# brush_driver.net
KiCad netlist of a schematic drawn in Altium Designer
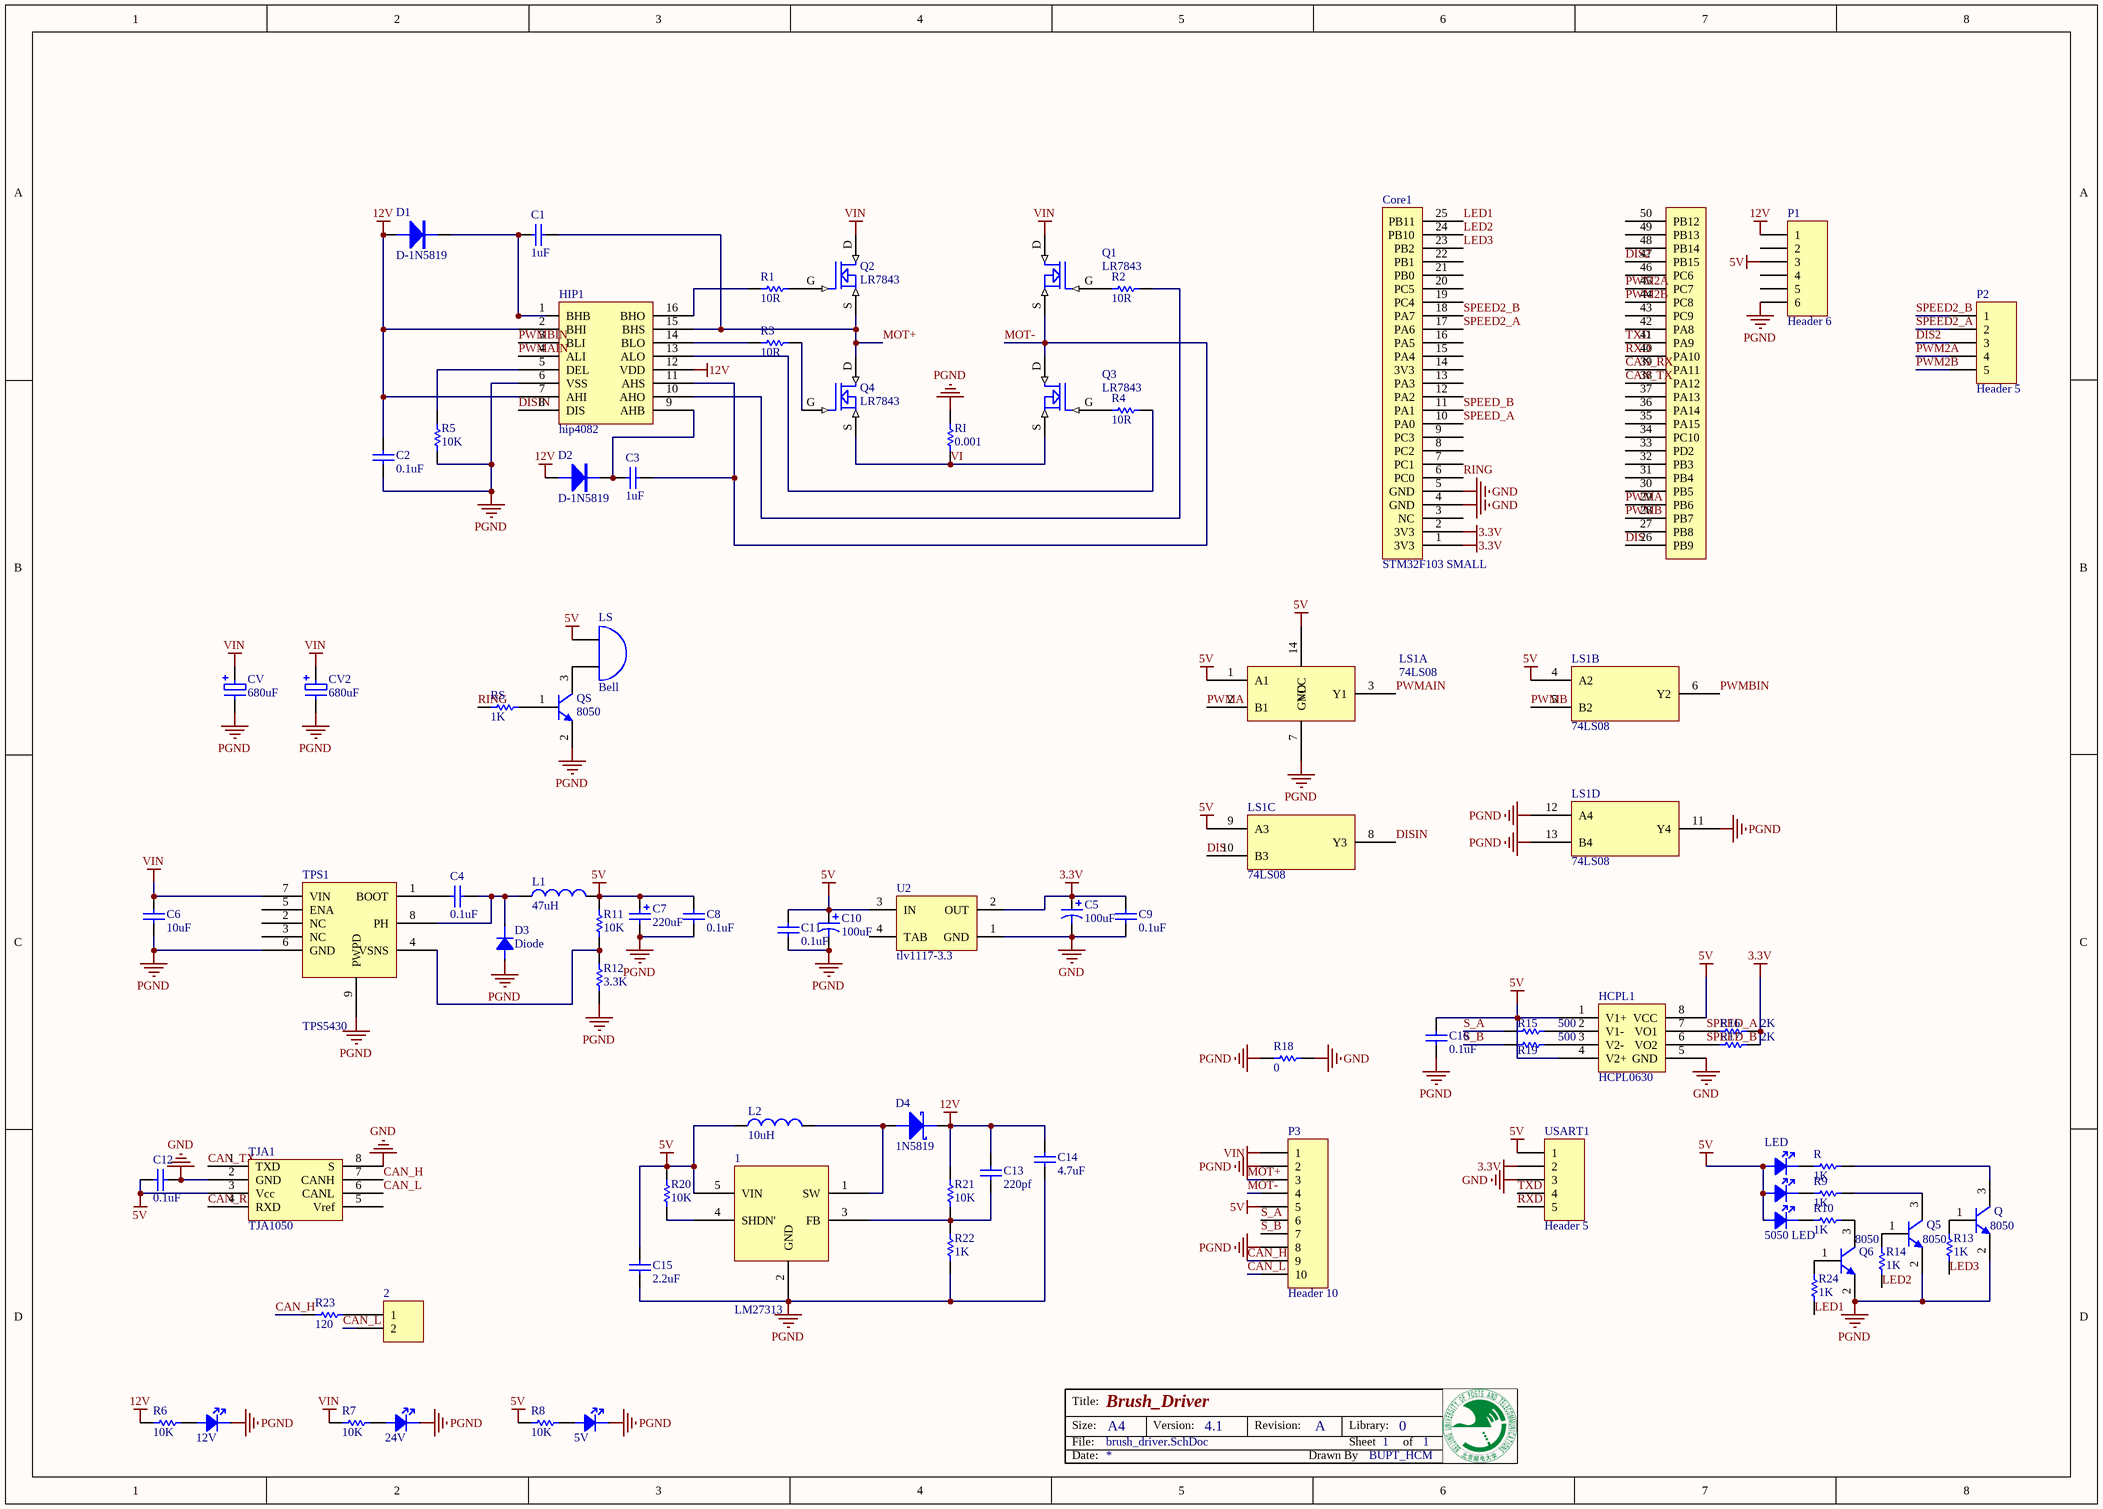
[diagram p0: brush_driver.SchDoc]

(export (version "E")
  (design (tool "Eeschema 10.0.6"))
  (components
    (comp (ref "1")
      (value "LM27313")
      (footprint "LM27313")
      (libsource (lib "K60-mainboard-v3.1") (part "LM27313"))
    )
    (comp (ref "2")
      (value "Header 2")
      (footprint "SIP2")
      (description "Header, 2-Pin")
      (fields (field (name "PUBLISHER") "Altium Limited"))
      (libsource (lib "Libraries_2014_0618") (part "Header 2"))
    )
    (comp (ref "5V")
      (value "lED")
      (footprint "0805D")
      (description "LED")
      (libsource (lib "K60-mainboard-v3.1") (part "00-D-LED"))
    )
    (comp (ref "12V")
      (value "lED")
      (footprint "0805D")
      (description "LED")
      (libsource (lib "K60-mainboard-v3.1") (part "00-D-LED"))
    )
    (comp (ref "24V")
      (value "lED")
      (footprint "0805D")
      (description "LED")
      (libsource (lib "K60-mainboard-v3.1") (part "00-D-LED"))
    )
    (comp (ref "C1")
      (value "1uF")
      (footprint "CAP-MLCC-0603")
      (description "Capacitor")
      (fields (field (name "Comment") "Cap") (field (name "PUBLISHER") "Altium Limited"))
      (libsource (lib "K60-mainboard-v3.1") (part "Cap"))
    )
    (comp (ref "C2")
      (value "0.1uF")
      (footprint "CAP-MLCC-0603")
      (description "Capacitor")
      (fields (field (name "Comment") "Cap") (field (name "PUBLISHER") "Altium Limited"))
      (libsource (lib "K60-mainboard-v3.1") (part "Cap"))
    )
    (comp (ref "C3")
      (value "1uF")
      (footprint "CAP-MLCC-0603")
      (description "Capacitor")
      (fields (field (name "Comment") "Cap") (field (name "PUBLISHER") "Altium Limited"))
      (libsource (lib "K60-mainboard-v3.1") (part "Cap"))
    )
    (comp (ref "C4")
      (value "0.1uF")
      (footprint "CAP-MLCC-0603")
      (description "Capacitor")
      (fields (field (name "Comment") "Cap") (field (name "PUBLISHER") "Altium Limited"))
      (libsource (lib "K60-mainboard-v3.1") (part "Cap"))
    )
    (comp (ref "C5")
      (value "100uF")
      (footprint "6032C")
      (description "Polarized Capacitor (Surface Mount)")
      (fields (field (name "Comment") "Cap Pol3") (field (name "PUBLISHER") "Altium Limited"))
      (libsource (lib "K60-mainboard-v3.1") (part "Cap Pol3"))
    )
    (comp (ref "C6")
      (value "10uF")
      (footprint "0805C")
      (description "Capacitor")
      (fields (field (name "Comment") "Cap") (field (name "PUBLISHER") "Altium Limited"))
      (libsource (lib "K60-mainboard-v3.1") (part "Cap"))
    )
    (comp (ref "C7")
      (value "220uF")
      (footprint "CAP-TAN-7343/CAPD")
      (description "Polarized Capacitor (Radial)")
      (fields (field (name "Comment") "Cap Pol1") (field (name "PUBLISHER") "Altium Limited"))
      (libsource (lib "K60-mainboard-v3.1") (part "Cap Pol1"))
    )
    (comp (ref "C8")
      (value "0.1uF")
      (footprint "CAP-MLCC-0603")
      (description "Capacitor")
      (fields (field (name "Comment") "Cap") (field (name "PUBLISHER") "Altium Limited"))
      (libsource (lib "K60-mainboard-v3.1") (part "Cap"))
    )
    (comp (ref "C9")
      (value "0.1uF")
      (footprint "CAP-MLCC-0603")
      (description "Capacitor")
      (fields (field (name "Comment") "Cap") (field (name "PUBLISHER") "Altium Limited"))
      (libsource (lib "K60-mainboard-v3.1") (part "Cap"))
    )
    (comp (ref "C10")
      (value "100uF")
      (footprint "6032C")
      (description "Polarized Capacitor (Surface Mount)")
      (fields (field (name "Comment") "Cap Pol3") (field (name "PUBLISHER") "Altium Limited"))
      (libsource (lib "K60-mainboard-v3.1") (part "Cap Pol3"))
    )
    (comp (ref "C11")
      (value "0.1uF")
      (footprint "CAP-MLCC-0603")
      (description "Capacitor")
      (fields (field (name "Comment") "Cap") (field (name "PUBLISHER") "Altium Limited"))
      (libsource (lib "K60-mainboard-v3.1") (part "Cap"))
    )
    (comp (ref "C12")
      (value "0.1uF")
      (footprint "CAP-MLCC-0603")
      (description "Capacitor")
      (fields (field (name "Comment") "Cap") (field (name "PUBLISHER") "Altium Limited"))
      (libsource (lib "K60-mainboard-v3.1") (part "Cap"))
    )
    (comp (ref "C13")
      (value "220pf")
      (footprint "CAP-MLCC-0603")
      (description "Capacitor")
      (fields (field (name "Comment") "Cap") (field (name "PUBLISHER") "Altium Limited"))
      (libsource (lib "K60-mainboard-v3.1") (part "Cap_1"))
    )
    (comp (ref "C14")
      (value "4.7uF")
      (footprint "CAP-MLCC-0603")
      (description "Capacitor")
      (fields (field (name "Comment") "Cap") (field (name "PUBLISHER") "Altium Limited"))
      (libsource (lib "K60-mainboard-v3.1") (part "Cap_1"))
    )
    (comp (ref "C15")
      (value "2.2uF")
      (footprint "CAP-MLCC-0603")
      (description "Capacitor")
      (fields (field (name "Comment") "Cap") (field (name "PUBLISHER") "Altium Limited"))
      (libsource (lib "K60-mainboard-v3.1") (part "Cap_1"))
    )
    (comp (ref "C16")
      (value "0.1uF")
      (footprint "CAP-MLCC-0603")
      (description "Capacitor")
      (fields (field (name "Comment") "Cap") (field (name "PUBLISHER") "Altium Limited"))
      (libsource (lib "K60-mainboard-v3.1") (part "Cap"))
    )
    (comp (ref "Core1")
      (value "STM32F103 SMALL")
      (footprint "STM32F103Small")
      (libsource (lib "K60-mainboard-v3.1") (part "STM32F103 SMALL"))
    )
    (comp (ref "CV")
      (value "680uF")
      (footprint "C_ELE")
      (description "电解电容")
      (fields (field (name "PUBLISHER") "Altium Limited"))
      (libsource (lib "Libraries_2014_0618") (part "CAP-ELE"))
    )
    (comp (ref "CV2")
      (value "680uF")
      (footprint "C_ELE")
      (description "电解电容")
      (fields (field (name "PUBLISHER") "Altium Limited"))
      (libsource (lib "Libraries_2014_0618") (part "CAP-ELE"))
    )
    (comp (ref "D1")
      (value "D-1N5819")
      (footprint "0805D")
      (description "Diode")
      (libsource (lib "常用器件") (part "D-1N5819"))
    )
    (comp (ref "D2")
      (value "D-1N5819")
      (footprint "0805D")
      (description "Diode")
      (libsource (lib "常用器件") (part "D-1N5819"))
    )
    (comp (ref "D3") (value "Diode") (footprint "SS34") (libsource (lib "K60-mainboard-v3.1") (part "Diode")))
    (comp (ref "D4")
      (value "1N5819")
      (footprint "0805D")
      (description "MBRA140T3")
      (libsource (lib "常用器件") (part "D-MBRA140T3"))
    )
    (comp (ref "HCPL1")
      (value "HCPL0630")
      (footprint "SOIC8")
      (libsource (lib "K60-mainboard-v3.1") (part "HCPL0630"))
    )
    (comp (ref "HIP1") (value "hip4082") (footprint "SOP16") (libsource (lib "元件库") (part "hip4082")))
    (comp (ref "L1")
      (value "47uH")
      (footprint "CD74")
      (description "Inductor")
      (fields (field (name "PUBLISHER") "Altium Limited"))
      (libsource (lib "smartcar_example") (part "Inductor"))
    )
    (comp (ref "L2")
      (value "10uH")
      (footprint "CD52")
      (description "Inductor")
      (fields (field (name "PUBLISHER") "Altium Limited"))
      (libsource (lib "smartcar_example") (part "Inductor"))
    )
    (comp (ref "LED")
      (value "5050 LED")
      (footprint "5050LED")
      (libsource (lib "K60-mainboard-v3.1") (part "5050 LED"))
    )
    (comp (ref "LS")
      (value "Bell")
      (footprint "Ring")
      (description "Electrical Bell")
      (fields (field (name "PUBLISHER") "Altium Limited"))
      (libsource (lib "附加元件") (part "Bell"))
    )
    (comp (ref "LS1")
      (value "74LS08")
      (footprint "SOJ-14")
      (libsource (lib "K60-mainboard-v3.1") (part "74LS08"))
    )
    (comp (ref "P1")
      (value "Header 6")
      (footprint "HDR1X6")
      (description "Header, 6-Pin")
      (fields (field (name "PUBLISHER") "Altium Limited"))
      (libsource (lib "K60-mainboard-v3.1") (part "Header 6"))
    )
    (comp (ref "P2")
      (value "Header 5")
      (footprint "HDR1X5")
      (description "Header, 5-Pin")
      (fields (field (name "PUBLISHER") "Altium Limited"))
      (libsource (lib "K60-mainboard-v3.1") (part "Header 5"))
    )
    (comp (ref "P3")
      (value "Header 10")
      (footprint "Green 10P")
      (description "Header, 10-Pin")
      (fields (field (name "PUBLISHER") "Altium Limited"))
      (libsource (lib "Libraries_2014_0618") (part "Header 10"))
    )
    (comp (ref "Q")
      (value "8050")
      (footprint "SOT-23B_N")
      (description "NPN Bipolar Transistor")
      (fields (field (name "PUBLISHER") "Altium Limited"))
      (libsource (lib "附加元件") (part "QNPN"))
    )
    (comp (ref "Q1")
      (value "LR7843")
      (footprint "LR7843")
      (libsource (lib "K60-mainboard-v3.1") (part "LR7843"))
    )
    (comp (ref "Q2")
      (value "LR7843")
      (footprint "LR7843")
      (libsource (lib "K60-mainboard-v3.1") (part "LR7843"))
    )
    (comp (ref "Q3")
      (value "LR7843")
      (footprint "LR7843")
      (libsource (lib "K60-mainboard-v3.1") (part "LR7843"))
    )
    (comp (ref "Q4")
      (value "LR7843")
      (footprint "LR7843")
      (libsource (lib "K60-mainboard-v3.1") (part "LR7843"))
    )
    (comp (ref "Q5")
      (value "8050")
      (footprint "SOT-23B_N")
      (description "NPN Bipolar Transistor")
      (fields (field (name "PUBLISHER") "Altium Limited"))
      (libsource (lib "附加元件") (part "QNPN"))
    )
    (comp (ref "Q6")
      (value "8050")
      (footprint "SOT-23B_N")
      (description "NPN Bipolar Transistor")
      (fields (field (name "PUBLISHER") "Altium Limited"))
      (libsource (lib "附加元件") (part "QNPN"))
    )
    (comp (ref "QS")
      (value "8050")
      (footprint "SOT-23B_N")
      (description "NPN Bipolar Transistor")
      (fields (field (name "PUBLISHER") "Altium Limited"))
      (libsource (lib "附加元件") (part "QNPN"))
    )
    (comp (ref "R")
      (value "1K")
      (footprint "RES-0603")
      (description "Resistor")
      (fields (field (name "Comment") "Res1") (field (name "PUBLISHER") "Altium Limited"))
      (libsource (lib "K60-mainboard-v3.1") (part "Res1"))
    )
    (comp (ref "R1")
      (value "10R")
      (footprint "RES-0603")
      (description "Resistor")
      (fields (field (name "Comment") "Res1") (field (name "PUBLISHER") "Altium Limited"))
      (libsource (lib "K60-mainboard-v3.1") (part "Res1"))
    )
    (comp (ref "R2")
      (value "10R")
      (footprint "RES-0603")
      (description "Resistor")
      (fields (field (name "Comment") "Res1") (field (name "PUBLISHER") "Altium Limited"))
      (libsource (lib "K60-mainboard-v3.1") (part "Res1"))
    )
    (comp (ref "R3")
      (value "10R")
      (footprint "RES-0603")
      (description "Resistor")
      (fields (field (name "Comment") "Res1") (field (name "PUBLISHER") "Altium Limited"))
      (libsource (lib "K60-mainboard-v3.1") (part "Res1"))
    )
    (comp (ref "R4")
      (value "10R")
      (footprint "RES-0603")
      (description "Resistor")
      (fields (field (name "Comment") "Res1") (field (name "PUBLISHER") "Altium Limited"))
      (libsource (lib "K60-mainboard-v3.1") (part "Res1"))
    )
    (comp (ref "R5")
      (value "10K")
      (footprint "RES-0603")
      (description "Resistor")
      (fields (field (name "Comment") "Res1") (field (name "PUBLISHER") "Altium Limited"))
      (libsource (lib "K60-mainboard-v3.1") (part "Res1"))
    )
    (comp (ref "R6")
      (value "10K")
      (footprint "RES-0603")
      (description "Resistor")
      (fields (field (name "Comment") "Res1") (field (name "PUBLISHER") "Altium Limited"))
      (libsource (lib "K60-mainboard-v3.1") (part "Res1"))
    )
    (comp (ref "R7")
      (value "10K")
      (footprint "RES-0603")
      (description "Resistor")
      (fields (field (name "Comment") "Res1") (field (name "PUBLISHER") "Altium Limited"))
      (libsource (lib "K60-mainboard-v3.1") (part "Res1"))
    )
    (comp (ref "R8")
      (value "10K")
      (footprint "RES-0603")
      (description "Resistor")
      (fields (field (name "Comment") "Res1") (field (name "PUBLISHER") "Altium Limited"))
      (libsource (lib "K60-mainboard-v3.1") (part "Res1"))
    )
    (comp (ref "R9")
      (value "1K")
      (footprint "RES-0603")
      (description "Resistor")
      (fields (field (name "Comment") "Res1") (field (name "PUBLISHER") "Altium Limited"))
      (libsource (lib "K60-mainboard-v3.1") (part "Res1"))
    )
    (comp (ref "R10")
      (value "1K")
      (footprint "RES-0603")
      (description "Resistor")
      (fields (field (name "Comment") "Res1") (field (name "PUBLISHER") "Altium Limited"))
      (libsource (lib "K60-mainboard-v3.1") (part "Res1"))
    )
    (comp (ref "R11")
      (value "10K")
      (footprint "RES-0603")
      (description "Resistor")
      (fields (field (name "Comment") "Res1") (field (name "PUBLISHER") "Altium Limited"))
      (libsource (lib "K60-mainboard-v3.1") (part "Res1"))
    )
    (comp (ref "R12")
      (value "3.3K")
      (footprint "RES-0603")
      (description "Resistor")
      (fields (field (name "Comment") "Res1") (field (name "PUBLISHER") "Altium Limited"))
      (libsource (lib "K60-mainboard-v3.1") (part "Res1"))
    )
    (comp (ref "R13")
      (value "1K")
      (footprint "RES-0603")
      (description "Resistor")
      (fields (field (name "Comment") "Res1") (field (name "PUBLISHER") "Altium Limited"))
      (libsource (lib "K60-mainboard-v3.1") (part "Res1"))
    )
    (comp (ref "R14")
      (value "1K")
      (footprint "RES-0603")
      (description "Resistor")
      (fields (field (name "Comment") "Res1") (field (name "PUBLISHER") "Altium Limited"))
      (libsource (lib "K60-mainboard-v3.1") (part "Res1"))
    )
    (comp (ref "R15")
      (value "500")
      (footprint "RES-0603")
      (description "Resistor")
      (fields (field (name "Comment") "Res1") (field (name "PUBLISHER") "Altium Limited"))
      (libsource (lib "K60-mainboard-v3.1") (part "Res1"))
    )
    (comp (ref "R16")
      (value "2K")
      (footprint "RES-0603")
      (description "Resistor")
      (fields (field (name "Comment") "Res1") (field (name "PUBLISHER") "Altium Limited"))
      (libsource (lib "K60-mainboard-v3.1") (part "Res1"))
    )
    (comp (ref "R17")
      (value "2K")
      (footprint "RES-0603")
      (description "Resistor")
      (fields (field (name "Comment") "Res1") (field (name "PUBLISHER") "Altium Limited"))
      (libsource (lib "K60-mainboard-v3.1") (part "Res1"))
    )
    (comp (ref "R18")
      (value "0")
      (footprint "RES-0603")
      (description "Resistor")
      (fields (field (name "Comment") "Res1") (field (name "PUBLISHER") "Altium Limited"))
      (libsource (lib "K60-mainboard-v3.1") (part "Res1"))
    )
    (comp (ref "R19")
      (value "500")
      (footprint "RES-0603")
      (description "Resistor")
      (fields (field (name "Comment") "Res1") (field (name "PUBLISHER") "Altium Limited"))
      (libsource (lib "K60-mainboard-v3.1") (part "Res1"))
    )
    (comp (ref "R20")
      (value "10K")
      (footprint "RES-0603")
      (description "Resistor")
      (fields (field (name "Comment") "Res1") (field (name "PUBLISHER") "Altium Limited"))
      (libsource (lib "K60-mainboard-v3.1") (part "Res1_1"))
    )
    (comp (ref "R21")
      (value "10K")
      (footprint "RES-0603")
      (description "Resistor")
      (fields (field (name "Comment") "Res1") (field (name "PUBLISHER") "Altium Limited"))
      (libsource (lib "K60-mainboard-v3.1") (part "Res1_1"))
    )
    (comp (ref "R22")
      (value "1K")
      (footprint "RES-0603")
      (description "Resistor")
      (fields (field (name "Comment") "Res1") (field (name "PUBLISHER") "Altium Limited"))
      (libsource (lib "K60-mainboard-v3.1") (part "Res1_1"))
    )
    (comp (ref "R23")
      (value "120")
      (footprint "RES-0603")
      (description "Resistor")
      (fields (field (name "Comment") "Res1") (field (name "PUBLISHER") "Altium Limited"))
      (libsource (lib "K60-mainboard-v3.1") (part "Res1"))
    )
    (comp (ref "R24")
      (value "1K")
      (footprint "RES-0603")
      (description "Resistor")
      (fields (field (name "Comment") "Res1") (field (name "PUBLISHER") "Altium Limited"))
      (libsource (lib "K60-mainboard-v3.1") (part "Res1"))
    )
    (comp (ref "RI")
      (value "0.001")
      (footprint "2512R")
      (description "Resistor")
      (fields (field (name "Comment") "Res1") (field (name "PUBLISHER") "Altium Limited"))
      (libsource (lib "K60-mainboard-v3.1") (part "Res1"))
    )
    (comp (ref "RS")
      (value "1K")
      (footprint "RES-0603")
      (description "Resistor")
      (fields (field (name "Comment") "Res1") (field (name "PUBLISHER") "Altium Limited"))
      (libsource (lib "K60-mainboard-v3.1") (part "Res1"))
    )
    (comp (ref "TJA1")
      (value "TJA1050")
      (footprint "TJA1050")
      (description "CAN总线收发器")
      (libsource (lib "Libraries_2014_0618") (part "TJA1050"))
    )
    (comp (ref "TPS1")
      (value "TPS5430")
      (footprint "TPS5430")
      (libsource (lib "K60-mainboard-v3.1") (part "TPS5430"))
    )
    (comp (ref "U2")
      (value "tlv1117-3.3")
      (footprint "LM1117")
      (description "800mA Low-Dropout Linear Regulator")
      (fields
        (field (name "PARTNUMBER") "LM1117IMP-5.0")
        (field (name "MANUFACTURER") "National Semiconductor")
        (field (name "PUBLISHER") "Altium Limited")
      )
      (libsource (lib "K60-mainboard-v3.1") (part "LM1117IMP-5.0"))
    )
    (comp (ref "USART1")
      (value "Header 5")
      (footprint "Green_5P")
      (description "Header, 5-Pin")
      (fields (field (name "PUBLISHER") "Altium Limited"))
      (libsource (lib "Libraries_2014_0618") (part "Header 5"))
    )
  )
  (nets
    (net (code "1") (name "/CAN_H") (class "Default")
      (node (ref "P3") (pin "9") (pinfunction "9_9") (pintype "passive"))
      (node (ref "R23") (pin "2") (pinfunction "2_2") (pintype "passive"))
      (node (ref "TJA1") (pin "7") (pinfunction "CANH_7") (pintype "passive"))
    )
    (net (code "2") (name "/CAN_L") (class "Default")
      (node (ref "2") (pin "2") (pinfunction "2_2") (pintype "passive"))
      (node (ref "P3") (pin "10") (pinfunction "10_10") (pintype "passive"))
      (node (ref "TJA1") (pin "6") (pinfunction "CANL_6") (pintype "passive"))
    )
    (net (code "3") (name "/CAN_RX") (class "Default")
      (node (ref "Core1") (pin "39") (pinfunction "PA11_39") (pintype "passive"))
      (node (ref "TJA1") (pin "4") (pinfunction "RXD_4") (pintype "passive"))
    )
    (net (code "4") (name "/CAN_TX") (class "Default")
      (node (ref "Core1") (pin "38") (pinfunction "PA12_38") (pintype "passive"))
      (node (ref "TJA1") (pin "1") (pinfunction "TXD_1") (pintype "passive"))
    )
    (net (code "5") (name "/DIS") (class "Default")
      (node (ref "Core1") (pin "26") (pinfunction "PB9_26") (pintype "passive"))
      (node (ref "LS1") (pin "10") (pinfunction "B3_10") (pintype "passive"))
    )
    (net (code "6") (name "/DIS2") (class "Default")
      (node (ref "Core1") (pin "47") (pinfunction "PB15_47") (pintype "passive"))
      (node (ref "P2") (pin "3") (pinfunction "3_3") (pintype "passive"))
    )
    (net (code "7") (name "/DISIN") (class "Default")
      (node (ref "HIP1") (pin "8") (pinfunction "DIS_8") (pintype "passive"))
      (node (ref "LS1") (pin "8") (pinfunction "Y3_8") (pintype "passive"))
    )
    (net (code "8") (name "/LED1") (class "Default")
      (node (ref "Core1") (pin "25") (pinfunction "PB11_25") (pintype "passive"))
      (node (ref "R24") (pin "2") (pinfunction "2_2") (pintype "passive"))
    )
    (net (code "9") (name "/LED2") (class "Default")
      (node (ref "Core1") (pin "24") (pinfunction "PB10_24") (pintype "passive"))
      (node (ref "R14") (pin "2") (pinfunction "2_2") (pintype "passive"))
    )
    (net (code "10") (name "/LED3") (class "Default")
      (node (ref "Core1") (pin "23") (pinfunction "PB2_23") (pintype "passive"))
      (node (ref "R13") (pin "2") (pinfunction "2_2") (pintype "passive"))
    )
    (net (code "11") (name "/MOT+") (class "Default")
      (node (ref "C1") (pin "1") (pinfunction "1_1") (pintype "passive"))
      (node (ref "HIP1") (pin "15") (pinfunction "BHS_15") (pintype "passive"))
      (node (ref "P3") (pin "3") (pinfunction "3_3") (pintype "passive"))
      (node (ref "Q2") (pin "S") (pinfunction "S_S") (pintype "input"))
      (node (ref "Q4") (pin "D") (pinfunction "D_D") (pintype "input"))
    )
    (net (code "12") (name "/MOT-") (class "Default")
      (node (ref "C3") (pin "1") (pinfunction "1_1") (pintype "passive"))
      (node (ref "HIP1") (pin "11") (pinfunction "AHS_11") (pintype "passive"))
      (node (ref "P3") (pin "4") (pinfunction "4_4") (pintype "passive"))
      (node (ref "Q1") (pin "S") (pinfunction "S_S") (pintype "input"))
      (node (ref "Q3") (pin "D") (pinfunction "D_D") (pintype "input"))
    )
    (net (code "13") (name "/PWM2A") (class "Default")
      (node (ref "Core1") (pin "45") (pinfunction "PC7_45") (pintype "passive"))
      (node (ref "P2") (pin "4") (pinfunction "4_4") (pintype "passive"))
    )
    (net (code "14") (name "/PWM2B") (class "Default")
      (node (ref "Core1") (pin "44") (pinfunction "PC8_44") (pintype "passive"))
      (node (ref "P2") (pin "5") (pinfunction "5_5") (pintype "passive"))
    )
    (net (code "15") (name "/PWMA") (class "Default")
      (node (ref "Core1") (pin "29") (pinfunction "PB6_29") (pintype "passive"))
      (node (ref "LS1") (pin "2") (pinfunction "B1_2") (pintype "passive"))
    )
    (net (code "16") (name "/PWMAIN") (class "Default")
      (node (ref "HIP1") (pin "4") (pinfunction "ALI_4") (pintype "passive"))
      (node (ref "LS1") (pin "3") (pinfunction "Y1_3") (pintype "passive"))
    )
    (net (code "17") (name "/PWMB") (class "Default")
      (node (ref "Core1") (pin "28") (pinfunction "PB7_28") (pintype "passive"))
      (node (ref "LS1") (pin "5") (pinfunction "B2_5") (pintype "passive"))
    )
    (net (code "18") (name "/PWMBIN") (class "Default")
      (node (ref "HIP1") (pin "3") (pinfunction "BLI_3") (pintype "passive"))
      (node (ref "LS1") (pin "6") (pinfunction "Y2_6") (pintype "passive"))
    )
    (net (code "19") (name "/RING") (class "Default")
      (node (ref "Core1") (pin "6") (pinfunction "PC0_6") (pintype "passive"))
      (node (ref "RS") (pin "2") (pinfunction "2_2") (pintype "passive"))
    )
    (net (code "20") (name "/RXD") (class "Default")
      (node (ref "Core1") (pin "40") (pinfunction "PA10_40") (pintype "passive"))
      (node (ref "USART1") (pin "5") (pinfunction "5_5") (pintype "passive"))
    )
    (net (code "21") (name "/SPEED2_A") (class "Default")
      (node (ref "Core1") (pin "17") (pinfunction "PA6_17") (pintype "passive"))
      (node (ref "P2") (pin "2") (pinfunction "2_2") (pintype "passive"))
    )
    (net (code "22") (name "/SPEED2_B") (class "Default")
      (node (ref "Core1") (pin "18") (pinfunction "PA7_18") (pintype "passive"))
      (node (ref "P2") (pin "1") (pinfunction "1_1") (pintype "passive"))
    )
    (net (code "23") (name "/SPEED_A") (class "Default")
      (node (ref "Core1") (pin "10") (pinfunction "PA0_10") (pintype "passive"))
      (node (ref "HCPL1") (pin "7") (pinfunction "VO1_7") (pintype "passive"))
      (node (ref "R16") (pin "1") (pinfunction "1_1") (pintype "passive"))
    )
    (net (code "24") (name "/SPEED_B") (class "Default")
      (node (ref "Core1") (pin "11") (pinfunction "PA1_11") (pintype "passive"))
      (node (ref "HCPL1") (pin "6") (pinfunction "VO2_6") (pintype "passive"))
      (node (ref "R17") (pin "1") (pinfunction "1_1") (pintype "passive"))
    )
    (net (code "25") (name "/S_A") (class "Default")
      (node (ref "P3") (pin "6") (pinfunction "6_6") (pintype "passive"))
      (node (ref "R15") (pin "1") (pinfunction "1_1") (pintype "passive"))
    )
    (net (code "26") (name "/S_B") (class "Default")
      (node (ref "P3") (pin "7") (pinfunction "7_7") (pintype "passive"))
      (node (ref "R19") (pin "1") (pinfunction "1_1") (pintype "passive"))
    )
    (net (code "27") (name "/TXD") (class "Default")
      (node (ref "Core1") (pin "41") (pinfunction "PA9_41") (pintype "passive"))
      (node (ref "USART1") (pin "4") (pinfunction "4_4") (pintype "passive"))
    )
    (net (code "28") (name "/VI") (class "Default")
      (node (ref "Q3") (pin "S") (pinfunction "S_S") (pintype "input"))
      (node (ref "Q4") (pin "S") (pinfunction "S_S") (pintype "input"))
      (node (ref "RI") (pin "1") (pinfunction "1_1") (pintype "passive"))
    )
    (net (code "29") (name "3.3V") (class "Default")
      (node (ref "C5") (pin "1") (pinfunction "1_1") (pintype "passive"))
      (node (ref "C9") (pin "1") (pinfunction "1_1") (pintype "passive"))
      (node (ref "Core1") (pin "1") (pinfunction "3V3_1") (pintype "passive"))
      (node (ref "Core1") (pin "2") (pinfunction "3V3_2") (pintype "passive"))
      (node (ref "R16") (pin "2") (pinfunction "2_2") (pintype "passive"))
      (node (ref "R17") (pin "2") (pinfunction "2_2") (pintype "passive"))
      (node (ref "U2") (pin "2") (pinfunction "OUT_2") (pintype "power_in"))
      (node (ref "USART1") (pin "2") (pinfunction "2_2") (pintype "passive"))
    )
    (net (code "30") (name "5V") (class "Default")
      (node (ref "1") (pin "5") (pinfunction "VIN_5") (pintype "passive"))
      (node (ref "C10") (pin "1") (pinfunction "1_1") (pintype "passive"))
      (node (ref "C11") (pin "1") (pinfunction "1_1") (pintype "passive"))
      (node (ref "C12") (pin "1") (pinfunction "1_1") (pintype "passive"))
      (node (ref "C15") (pin "2") (pinfunction "2_2") (pintype "passive"))
      (node (ref "C16") (pin "1") (pinfunction "1_1") (pintype "passive"))
      (node (ref "C7") (pin "1") (pinfunction "1_1") (pintype "passive"))
      (node (ref "C8") (pin "2") (pinfunction "2_2") (pintype "passive"))
      (node (ref "HCPL1") (pin "1") (pinfunction "V1+_1") (pintype "passive"))
      (node (ref "HCPL1") (pin "4") (pinfunction "V2+_4") (pintype "passive"))
      (node (ref "HCPL1") (pin "8") (pinfunction "VCC_8") (pintype "passive"))
      (node (ref "L1") (pin "2") (pinfunction "2_2") (pintype "passive"))
      (node (ref "L2") (pin "1") (pinfunction "1_1") (pintype "passive"))
      (node (ref "LED") (pin "A1") (pinfunction "1_A1") (pintype "passive"))
      (node (ref "LED") (pin "A2") (pinfunction "3_A2") (pintype "passive"))
      (node (ref "LED") (pin "A3") (pinfunction "5_A3") (pintype "passive"))
      (node (ref "LS") (pin "1") (pinfunction "A_1") (pintype "passive"))
      (node (ref "LS1") (pin "1") (pinfunction "A1_1") (pintype "passive"))
      (node (ref "LS1") (pin "14") (pinfunction "VCC_14") (pintype "passive"))
      (node (ref "LS1") (pin "4") (pinfunction "A2_4") (pintype "passive"))
      (node (ref "LS1") (pin "9") (pinfunction "A3_9") (pintype "passive"))
      (node (ref "P1") (pin "3") (pinfunction "3_3") (pintype "passive"))
      (node (ref "P3") (pin "5") (pinfunction "5_5") (pintype "passive"))
      (node (ref "R11") (pin "2") (pinfunction "2_2") (pintype "passive"))
      (node (ref "R20") (pin "1") (pinfunction "1_1") (pintype "passive"))
      (node (ref "R8") (pin "2") (pinfunction "2_2") (pintype "passive"))
      (node (ref "TJA1") (pin "3") (pinfunction "Vcc_3") (pintype "passive"))
      (node (ref "U2") (pin "3") (pinfunction "IN_3") (pintype "power_in"))
      (node (ref "USART1") (pin "1") (pinfunction "1_1") (pintype "passive"))
    )
    (net (code "31") (name "12V") (class "Default")
      (node (ref "C13") (pin "2") (pinfunction "2_2") (pintype "passive"))
      (node (ref "C14") (pin "2") (pinfunction "2_2") (pintype "passive"))
      (node (ref "C2") (pin "2") (pinfunction "2_2") (pintype "passive"))
      (node (ref "D1") (pin "A") (pinfunction "1_A") (pintype "passive"))
      (node (ref "D2") (pin "A") (pinfunction "1_A") (pintype "passive"))
      (node (ref "D4") (pin "K") (pinfunction "2_K") (pintype "passive"))
      (node (ref "HIP1") (pin "12") (pinfunction "VDD_12") (pintype "passive"))
      (node (ref "HIP1") (pin "2") (pinfunction "BHI_2") (pintype "passive"))
      (node (ref "HIP1") (pin "7") (pinfunction "AHI_7") (pintype "passive"))
      (node (ref "P1") (pin "1") (pinfunction "1_1") (pintype "passive"))
      (node (ref "R21") (pin "1") (pinfunction "1_1") (pintype "passive"))
      (node (ref "R6") (pin "2") (pinfunction "2_2") (pintype "passive"))
    )
    (net (code "32") (name "GND") (class "Default")
      (node (ref "C12") (pin "2") (pinfunction "2_2") (pintype "passive"))
      (node (ref "C5") (pin "2") (pinfunction "2_2") (pintype "passive"))
      (node (ref "C9") (pin "2") (pinfunction "2_2") (pintype "passive"))
      (node (ref "Core1") (pin "4") (pinfunction "GND_4") (pintype "passive"))
      (node (ref "Core1") (pin "5") (pinfunction "GND_5") (pintype "passive"))
      (node (ref "HCPL1") (pin "5") (pinfunction "GND_5") (pintype "passive"))
      (node (ref "R18") (pin "2") (pinfunction "2_2") (pintype "passive"))
      (node (ref "TJA1") (pin "2") (pinfunction "GND_2") (pintype "passive"))
      (node (ref "TJA1") (pin "8") (pinfunction "S_8") (pintype "passive"))
      (node (ref "U2") (pin "1") (pinfunction "GND_1") (pintype "power_in"))
      (node (ref "USART1") (pin "3") (pinfunction "3_3") (pintype "passive"))
    )
    (net (code "33") (name "Net-(1-FB)") (class "Default")
      (node (ref "1") (pin "3") (pinfunction "FB_3") (pintype "passive"))
      (node (ref "C13") (pin "1") (pinfunction "1_1") (pintype "passive"))
      (node (ref "R21") (pin "2") (pinfunction "2_2") (pintype "passive"))
      (node (ref "R22") (pin "1") (pinfunction "1_1") (pintype "passive"))
    )
    (net (code "34") (name "Net-(1-SHDN')") (class "Default")
      (node (ref "1") (pin "4") (pinfunction "SHDN'_4") (pintype "passive"))
      (node (ref "R20") (pin "2") (pinfunction "2_2") (pintype "passive"))
    )
    (net (code "35") (name "Net-(1-SW)") (class "Default")
      (node (ref "1") (pin "1") (pinfunction "SW_1") (pintype "passive"))
      (node (ref "D4") (pin "A") (pinfunction "1_A") (pintype "passive"))
      (node (ref "L2") (pin "2") (pinfunction "2_2") (pintype "passive"))
    )
    (net (code "36") (name "Net-(2-Pad1)") (class "Default")
      (node (ref "2") (pin "1") (pinfunction "1_1") (pintype "passive"))
      (node (ref "R23") (pin "1") (pinfunction "1_1") (pintype "passive"))
    )
    (net (code "37") (name "Net-(5V-1)") (class "Default")
      (node (ref "5V") (pin "A") (pinfunction "1_A") (pintype "passive"))
      (node (ref "R8") (pin "1") (pinfunction "1_1") (pintype "passive"))
    )
    (net (code "38") (name "Net-(12V-1)") (class "Default")
      (node (ref "12V") (pin "A") (pinfunction "1_A") (pintype "passive"))
      (node (ref "R6") (pin "1") (pinfunction "1_1") (pintype "passive"))
    )
    (net (code "39") (name "Net-(24V-1)") (class "Default")
      (node (ref "24V") (pin "A") (pinfunction "1_A") (pintype "passive"))
      (node (ref "R7") (pin "1") (pinfunction "1_1") (pintype "passive"))
    )
    (net (code "40") (name "Net-(D1-2)") (class "Default")
      (node (ref "C1") (pin "2") (pinfunction "2_2") (pintype "passive"))
      (node (ref "D1") (pin "K") (pinfunction "2_K") (pintype "passive"))
      (node (ref "HIP1") (pin "1") (pinfunction "BHB_1") (pintype "passive"))
    )
    (net (code "41") (name "Net-(D2-2)") (class "Default")
      (node (ref "C3") (pin "2") (pinfunction "2_2") (pintype "passive"))
      (node (ref "D2") (pin "K") (pinfunction "2_K") (pintype "passive"))
      (node (ref "HIP1") (pin "9") (pinfunction "AHB_9") (pintype "passive"))
    )
    (net (code "42") (name "Net-(D3-2)") (class "Default")
      (node (ref "C4") (pin "2") (pinfunction "2_2") (pintype "passive"))
      (node (ref "D3") (pin "K") (pinfunction "2_K") (pintype "passive"))
      (node (ref "L1") (pin "1") (pinfunction "1_1") (pintype "passive"))
      (node (ref "TPS1") (pin "8") (pinfunction "PH_8") (pintype "passive"))
    )
    (net (code "43") (name "Net-(HCPL1-V1-)") (class "Default")
      (node (ref "HCPL1") (pin "2") (pinfunction "V1-_2") (pintype "passive"))
      (node (ref "R15") (pin "2") (pinfunction "2_2") (pintype "passive"))
    )
    (net (code "44") (name "Net-(HCPL1-V2-)") (class "Default")
      (node (ref "HCPL1") (pin "3") (pinfunction "V2-_3") (pintype "passive"))
      (node (ref "R19") (pin "2") (pinfunction "2_2") (pintype "passive"))
    )
    (net (code "45") (name "Net-(HIP1-AHO)") (class "Default")
      (node (ref "HIP1") (pin "10") (pinfunction "AHO_10") (pintype "passive"))
      (node (ref "R2") (pin "2") (pinfunction "2_2") (pintype "passive"))
    )
    (net (code "46") (name "Net-(HIP1-ALO)") (class "Default")
      (node (ref "HIP1") (pin "13") (pinfunction "ALO_13") (pintype "passive"))
      (node (ref "R4") (pin "2") (pinfunction "2_2") (pintype "passive"))
    )
    (net (code "47") (name "Net-(HIP1-BHO)") (class "Default")
      (node (ref "HIP1") (pin "16") (pinfunction "BHO_16") (pintype "passive"))
      (node (ref "R1") (pin "2") (pinfunction "2_2") (pintype "passive"))
    )
    (net (code "48") (name "Net-(HIP1-BLO)") (class "Default")
      (node (ref "HIP1") (pin "14") (pinfunction "BLO_14") (pintype "passive"))
      (node (ref "R3") (pin "1") (pinfunction "1_1") (pintype "passive"))
    )
    (net (code "49") (name "Net-(HIP1-DEL)") (class "Default")
      (node (ref "HIP1") (pin "5") (pinfunction "DEL_5") (pintype "passive"))
      (node (ref "R5") (pin "2") (pinfunction "2_2") (pintype "passive"))
    )
    (net (code "50") (name "Net-(LED-2)") (class "Default")
      (node (ref "LED") (pin "K1") (pinfunction "2_K1") (pintype "passive"))
      (node (ref "R") (pin "2") (pinfunction "2_2") (pintype "passive"))
    )
    (net (code "51") (name "Net-(LED-4)") (class "Default")
      (node (ref "LED") (pin "K2") (pinfunction "4_K2") (pintype "passive"))
      (node (ref "R9") (pin "2") (pinfunction "2_2") (pintype "passive"))
    )
    (net (code "52") (name "Net-(LED-6)") (class "Default")
      (node (ref "LED") (pin "K3") (pinfunction "6_K3") (pintype "passive"))
      (node (ref "R10") (pin "2") (pinfunction "2_2") (pintype "passive"))
    )
    (net (code "53") (name "Net-(LS-B)") (class "Default")
      (node (ref "LS") (pin "2") (pinfunction "B_2") (pintype "passive"))
      (node (ref "QS") (pin "3") (pinfunction "C_3") (pintype "passive"))
    )
    (net (code "54") (name "Net-(Q-B)") (class "Default")
      (node (ref "Q") (pin "1") (pinfunction "B_1") (pintype "passive"))
      (node (ref "R13") (pin "1") (pinfunction "1_1") (pintype "passive"))
    )
    (net (code "55") (name "Net-(Q-C)") (class "Default")
      (node (ref "Q") (pin "3") (pinfunction "C_3") (pintype "passive"))
      (node (ref "R") (pin "1") (pinfunction "1_1") (pintype "passive"))
    )
    (net (code "56") (name "Net-(Q1-PadG)") (class "Default")
      (node (ref "Q1") (pin "G") (pinfunction "G_G") (pintype "input"))
      (node (ref "R2") (pin "1") (pinfunction "1_1") (pintype "passive"))
    )
    (net (code "57") (name "Net-(Q2-PadG)") (class "Default")
      (node (ref "Q2") (pin "G") (pinfunction "G_G") (pintype "input"))
      (node (ref "R1") (pin "1") (pinfunction "1_1") (pintype "passive"))
    )
    (net (code "58") (name "Net-(Q3-PadG)") (class "Default")
      (node (ref "Q3") (pin "G") (pinfunction "G_G") (pintype "input"))
      (node (ref "R4") (pin "1") (pinfunction "1_1") (pintype "passive"))
    )
    (net (code "59") (name "Net-(Q4-PadG)") (class "Default")
      (node (ref "Q4") (pin "G") (pinfunction "G_G") (pintype "input"))
      (node (ref "R3") (pin "2") (pinfunction "2_2") (pintype "passive"))
    )
    (net (code "60") (name "Net-(Q5-B)") (class "Default")
      (node (ref "Q5") (pin "1") (pinfunction "B_1") (pintype "passive"))
      (node (ref "R14") (pin "1") (pinfunction "1_1") (pintype "passive"))
    )
    (net (code "61") (name "Net-(Q5-C)") (class "Default")
      (node (ref "Q5") (pin "3") (pinfunction "C_3") (pintype "passive"))
      (node (ref "R9") (pin "1") (pinfunction "1_1") (pintype "passive"))
    )
    (net (code "62") (name "Net-(Q6-B)") (class "Default")
      (node (ref "Q6") (pin "1") (pinfunction "B_1") (pintype "passive"))
      (node (ref "R24") (pin "1") (pinfunction "1_1") (pintype "passive"))
    )
    (net (code "63") (name "Net-(Q6-C)") (class "Default")
      (node (ref "Q6") (pin "3") (pinfunction "C_3") (pintype "passive"))
      (node (ref "R10") (pin "1") (pinfunction "1_1") (pintype "passive"))
    )
    (net (code "64") (name "Net-(QS-B)") (class "Default")
      (node (ref "QS") (pin "1") (pinfunction "B_1") (pintype "passive"))
      (node (ref "RS") (pin "1") (pinfunction "1_1") (pintype "passive"))
    )
    (net (code "65") (name "Net-(TPS1-BOOT)") (class "Default")
      (node (ref "C4") (pin "1") (pinfunction "1_1") (pintype "passive"))
      (node (ref "TPS1") (pin "1") (pinfunction "BOOT_1") (pintype "passive"))
    )
    (net (code "66") (name "Net-(TPS1-VSNS)") (class "Default")
      (node (ref "R11") (pin "1") (pinfunction "1_1") (pintype "passive"))
      (node (ref "R12") (pin "2") (pinfunction "2_2") (pintype "passive"))
      (node (ref "TPS1") (pin "4") (pinfunction "VSNS_4") (pintype "passive"))
    )
    (net (code "67") (name "PGND") (class "Default")
      (node (ref "1") (pin "2") (pinfunction "GND_2") (pintype "passive"))
      (node (ref "12V") (pin "K") (pinfunction "2_K") (pintype "passive"))
      (node (ref "24V") (pin "K") (pinfunction "2_K") (pintype "passive"))
      (node (ref "5V") (pin "K") (pinfunction "2_K") (pintype "passive"))
      (node (ref "C10") (pin "2") (pinfunction "2_2") (pintype "passive"))
      (node (ref "C11") (pin "2") (pinfunction "2_2") (pintype "passive"))
      (node (ref "C14") (pin "1") (pinfunction "1_1") (pintype "passive"))
      (node (ref "C15") (pin "1") (pinfunction "1_1") (pintype "passive"))
      (node (ref "C16") (pin "2") (pinfunction "2_2") (pintype "passive"))
      (node (ref "C2") (pin "1") (pinfunction "1_1") (pintype "passive"))
      (node (ref "C6") (pin "1") (pinfunction "1_1") (pintype "passive"))
      (node (ref "C7") (pin "2") (pinfunction "2_2") (pintype "passive"))
      (node (ref "C8") (pin "1") (pinfunction "1_1") (pintype "passive"))
      (node (ref "CV") (pin "2") (pinfunction "2_2") (pintype "passive"))
      (node (ref "CV2") (pin "2") (pinfunction "2_2") (pintype "passive"))
      (node (ref "D3") (pin "A") (pinfunction "1_A") (pintype "passive"))
      (node (ref "HIP1") (pin "6") (pinfunction "VSS_6") (pintype "passive"))
      (node (ref "LS1") (pin "11") (pinfunction "Y4_11") (pintype "passive"))
      (node (ref "LS1") (pin "12") (pinfunction "A4_12") (pintype "passive"))
      (node (ref "LS1") (pin "13") (pinfunction "B4_13") (pintype "passive"))
      (node (ref "LS1") (pin "7") (pinfunction "GND_7") (pintype "passive"))
      (node (ref "P1") (pin "6") (pinfunction "6_6") (pintype "passive"))
      (node (ref "P3") (pin "2") (pinfunction "2_2") (pintype "passive"))
      (node (ref "P3") (pin "8") (pinfunction "8_8") (pintype "passive"))
      (node (ref "Q") (pin "2") (pinfunction "E_2") (pintype "passive"))
      (node (ref "Q5") (pin "2") (pinfunction "E_2") (pintype "passive"))
      (node (ref "Q6") (pin "2") (pinfunction "E_2") (pintype "passive"))
      (node (ref "QS") (pin "2") (pinfunction "E_2") (pintype "passive"))
      (node (ref "R12") (pin "1") (pinfunction "1_1") (pintype "passive"))
      (node (ref "R18") (pin "1") (pinfunction "1_1") (pintype "passive"))
      (node (ref "R22") (pin "2") (pinfunction "2_2") (pintype "passive"))
      (node (ref "R5") (pin "1") (pinfunction "1_1") (pintype "passive"))
      (node (ref "RI") (pin "2") (pinfunction "2_2") (pintype "passive"))
      (node (ref "TPS1") (pin "6") (pinfunction "GND_6") (pintype "passive"))
      (node (ref "TPS1") (pin "9") (pinfunction "PWPD_9") (pintype "passive"))
    )
    (net (code "68") (name "VIN") (class "Default")
      (node (ref "C6") (pin "2") (pinfunction "2_2") (pintype "passive"))
      (node (ref "CV") (pin "1") (pinfunction "1_1") (pintype "passive"))
      (node (ref "CV2") (pin "1") (pinfunction "1_1") (pintype "passive"))
      (node (ref "P3") (pin "1") (pinfunction "1_1") (pintype "passive"))
      (node (ref "Q1") (pin "D") (pinfunction "D_D") (pintype "input"))
      (node (ref "Q2") (pin "D") (pinfunction "D_D") (pintype "input"))
      (node (ref "R7") (pin "2") (pinfunction "2_2") (pintype "passive"))
      (node (ref "TPS1") (pin "7") (pinfunction "VIN_7") (pintype "passive"))
    )
    (net (code "69") (name "unconnected-(Core1-3V3-Pad14)") (class "Default")
      (node (ref "Core1") (pin "14") (pinfunction "3V3_14") (pintype "passive"))
    )
    (net (code "70") (name "unconnected-(Core1-NC-Pad3)") (class "Default")
      (node (ref "Core1") (pin "3") (pinfunction "NC_3") (pintype "passive"))
    )
    (net (code "71") (name "unconnected-(Core1-PA2-Pad12)") (class "Default")
      (node (ref "Core1") (pin "12") (pinfunction "PA2_12") (pintype "passive"))
    )
    (net (code "72") (name "unconnected-(Core1-PA3-Pad13)") (class "Default")
      (node (ref "Core1") (pin "13") (pinfunction "PA3_13") (pintype "passive"))
    )
    (net (code "73") (name "unconnected-(Core1-PA4-Pad15)") (class "Default")
      (node (ref "Core1") (pin "15") (pinfunction "PA4_15") (pintype "passive"))
    )
    (net (code "74") (name "unconnected-(Core1-PA5-Pad16)") (class "Default")
      (node (ref "Core1") (pin "16") (pinfunction "PA5_16") (pintype "passive"))
    )
    (net (code "75") (name "unconnected-(Core1-PA8-Pad42)") (class "Default")
      (node (ref "Core1") (pin "42") (pinfunction "PA8_42") (pintype "passive"))
    )
    (net (code "76") (name "unconnected-(Core1-PA13-Pad37)") (class "Default")
      (node (ref "Core1") (pin "37") (pinfunction "PA13_37") (pintype "passive"))
    )
    (net (code "77") (name "unconnected-(Core1-PA14-Pad36)") (class "Default")
      (node (ref "Core1") (pin "36") (pinfunction "PA14_36") (pintype "passive"))
    )
    (net (code "78") (name "unconnected-(Core1-PA15-Pad35)") (class "Default")
      (node (ref "Core1") (pin "35") (pinfunction "PA15_35") (pintype "passive"))
    )
    (net (code "79") (name "unconnected-(Core1-PB0-Pad21)") (class "Default")
      (node (ref "Core1") (pin "21") (pinfunction "PB0_21") (pintype "passive"))
    )
    (net (code "80") (name "unconnected-(Core1-PB1-Pad22)") (class "Default")
      (node (ref "Core1") (pin "22") (pinfunction "PB1_22") (pintype "passive"))
    )
    (net (code "81") (name "unconnected-(Core1-PB3-Pad32)") (class "Default")
      (node (ref "Core1") (pin "32") (pinfunction "PB3_32") (pintype "passive"))
    )
    (net (code "82") (name "unconnected-(Core1-PB4-Pad31)") (class "Default")
      (node (ref "Core1") (pin "31") (pinfunction "PB4_31") (pintype "passive"))
    )
    (net (code "83") (name "unconnected-(Core1-PB5-Pad30)") (class "Default")
      (node (ref "Core1") (pin "30") (pinfunction "PB5_30") (pintype "passive"))
    )
    (net (code "84") (name "unconnected-(Core1-PB8-Pad27)") (class "Default")
      (node (ref "Core1") (pin "27") (pinfunction "PB8_27") (pintype "passive"))
    )
    (net (code "85") (name "unconnected-(Core1-PB12-Pad50)") (class "Default")
      (node (ref "Core1") (pin "50") (pinfunction "PB12_50") (pintype "passive"))
    )
    (net (code "86") (name "unconnected-(Core1-PB13-Pad49)") (class "Default")
      (node (ref "Core1") (pin "49") (pinfunction "PB13_49") (pintype "passive"))
    )
    (net (code "87") (name "unconnected-(Core1-PB14-Pad48)") (class "Default")
      (node (ref "Core1") (pin "48") (pinfunction "PB14_48") (pintype "passive"))
    )
    (net (code "88") (name "unconnected-(Core1-PC1-Pad7)") (class "Default")
      (node (ref "Core1") (pin "7") (pinfunction "PC1_7") (pintype "passive"))
    )
    (net (code "89") (name "unconnected-(Core1-PC2-Pad8)") (class "Default")
      (node (ref "Core1") (pin "8") (pinfunction "PC2_8") (pintype "passive"))
    )
    (net (code "90") (name "unconnected-(Core1-PC3-Pad9)") (class "Default")
      (node (ref "Core1") (pin "9") (pinfunction "PC3_9") (pintype "passive"))
    )
    (net (code "91") (name "unconnected-(Core1-PC4-Pad19)") (class "Default")
      (node (ref "Core1") (pin "19") (pinfunction "PC4_19") (pintype "passive"))
    )
    (net (code "92") (name "unconnected-(Core1-PC5-Pad20)") (class "Default")
      (node (ref "Core1") (pin "20") (pinfunction "PC5_20") (pintype "passive"))
    )
    (net (code "93") (name "unconnected-(Core1-PC6-Pad46)") (class "Default")
      (node (ref "Core1") (pin "46") (pinfunction "PC6_46") (pintype "passive"))
    )
    (net (code "94") (name "unconnected-(Core1-PC9-Pad43)") (class "Default")
      (node (ref "Core1") (pin "43") (pinfunction "PC9_43") (pintype "passive"))
    )
    (net (code "95") (name "unconnected-(Core1-PC10-Pad34)") (class "Default")
      (node (ref "Core1") (pin "34") (pinfunction "PC10_34") (pintype "passive"))
    )
    (net (code "96") (name "unconnected-(Core1-PD2-Pad33)") (class "Default")
      (node (ref "Core1") (pin "33") (pinfunction "PD2_33") (pintype "passive"))
    )
    (net (code "97") (name "unconnected-(P1-Pad2)") (class "Default")
      (node (ref "P1") (pin "2") (pinfunction "2_2") (pintype "passive"))
    )
    (net (code "98") (name "unconnected-(P1-Pad4)") (class "Default")
      (node (ref "P1") (pin "4") (pinfunction "4_4") (pintype "passive"))
    )
    (net (code "99") (name "unconnected-(P1-Pad5)") (class "Default")
      (node (ref "P1") (pin "5") (pinfunction "5_5") (pintype "passive"))
    )
    (net (code "100") (name "unconnected-(TJA1-Vref-Pad5)") (class "Default")
      (node (ref "TJA1") (pin "5") (pinfunction "Vref_5") (pintype "passive"))
    )
    (net (code "101") (name "unconnected-(TPS1-ENA-Pad5)") (class "Default")
      (node (ref "TPS1") (pin "5") (pinfunction "ENA_5") (pintype "passive"))
    )
    (net (code "102") (name "unconnected-(TPS1-NC-Pad2)") (class "Default")
      (node (ref "TPS1") (pin "2") (pinfunction "NC_2") (pintype "passive"))
    )
    (net (code "103") (name "unconnected-(TPS1-NC-Pad3)") (class "Default")
      (node (ref "TPS1") (pin "3") (pinfunction "NC_3") (pintype "passive"))
    )
    (net (code "104") (name "unconnected-(U2-TAB-Pad4)") (class "Default")
      (node (ref "U2") (pin "4") (pinfunction "TAB_4") (pintype "power_in"))
    )
  )
)
